# Backplane_v2.net
KiCad netlist of a schematic drawn in EAGLE
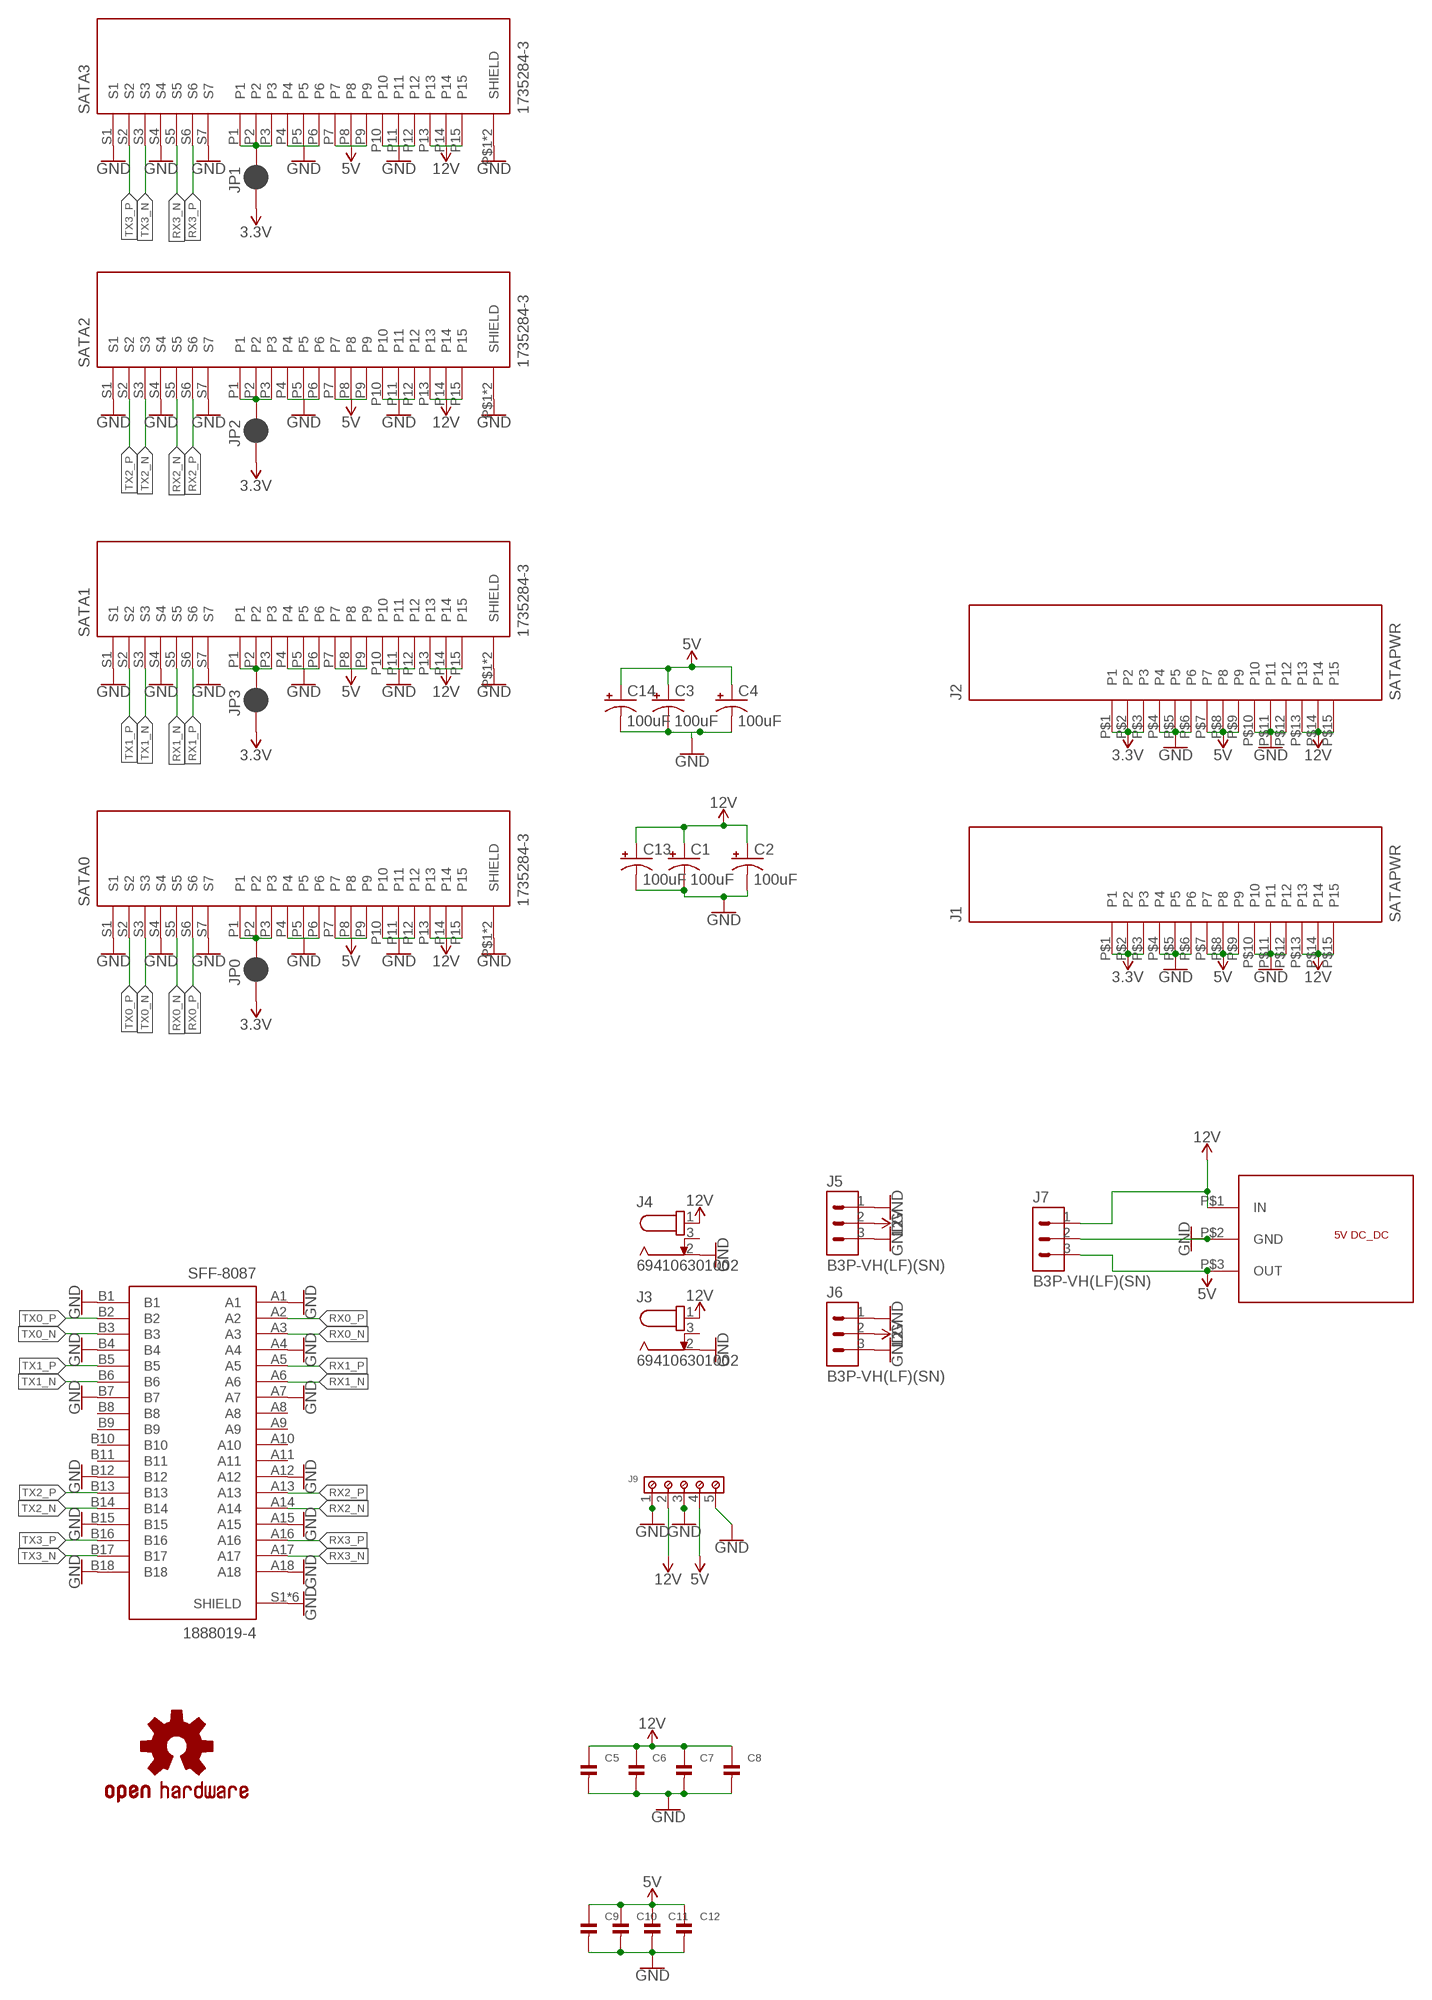
[diagram p0: schematic, sheet 1]

(export (version "E")
  (design (tool "Eeschema 10.0.6"))
  (components
    (comp (ref "C1")
      (value "100uF")
      (footprint "eagle-import:PANASONIC_D")
      (libsource (lib "eagle-import") (part "100UF-POLAR-25V-20%(ELEC)"))
    )
    (comp (ref "C2")
      (value "100uF")
      (footprint "eagle-import:PANASONIC_D")
      (libsource (lib "eagle-import") (part "100UF-POLAR-25V-20%(ELEC)"))
    )
    (comp (ref "C3")
      (value "100uF")
      (footprint "eagle-import:PANASONIC_D")
      (libsource (lib "eagle-import") (part "100UF-POLAR-25V-20%(ELEC)"))
    )
    (comp (ref "C4")
      (value "100uF")
      (footprint "eagle-import:PANASONIC_D")
      (libsource (lib "eagle-import") (part "100UF-POLAR-25V-20%(ELEC)"))
    )
    (comp (ref "C5")
      (value "CAP_CERAMIC0805")
      (footprint "eagle-import:C0805")
      (libsource (lib "eagle-import") (part "CAP_CERAMIC0805"))
    )
    (comp (ref "C6")
      (value "CAP_CERAMIC0805")
      (footprint "eagle-import:C0805")
      (libsource (lib "eagle-import") (part "CAP_CERAMIC0805"))
    )
    (comp (ref "C7")
      (value "CAP_CERAMIC0805")
      (footprint "eagle-import:C0805")
      (libsource (lib "eagle-import") (part "CAP_CERAMIC0805"))
    )
    (comp (ref "C8")
      (value "CAP_CERAMIC0805")
      (footprint "eagle-import:C0805")
      (libsource (lib "eagle-import") (part "CAP_CERAMIC0805"))
    )
    (comp (ref "C9")
      (value "CAP_CERAMIC0805")
      (footprint "eagle-import:C0805")
      (libsource (lib "eagle-import") (part "CAP_CERAMIC0805"))
    )
    (comp (ref "C10")
      (value "CAP_CERAMIC0805")
      (footprint "eagle-import:C0805")
      (libsource (lib "eagle-import") (part "CAP_CERAMIC0805"))
    )
    (comp (ref "C11")
      (value "CAP_CERAMIC0805")
      (footprint "eagle-import:C0805")
      (libsource (lib "eagle-import") (part "CAP_CERAMIC0805"))
    )
    (comp (ref "C12")
      (value "CAP_CERAMIC0805")
      (footprint "eagle-import:C0805")
      (libsource (lib "eagle-import") (part "CAP_CERAMIC0805"))
    )
    (comp (ref "C13")
      (value "100uF")
      (footprint "eagle-import:PANASONIC_D")
      (libsource (lib "eagle-import") (part "100UF-POLAR-25V-20%(ELEC)"))
    )
    (comp (ref "C14")
      (value "100uF")
      (footprint "eagle-import:PANASONIC_D")
      (libsource (lib "eagle-import") (part "100UF-POLAR-25V-20%(ELEC)"))
    )
    (comp (ref "J1")
      (value "SATAPWR")
      (footprint "eagle-import:PTH_90")
      (libsource (lib "eagle-import") (part "SATAPWR"))
    )
    (comp (ref "J2")
      (value "SATAPWR")
      (footprint "eagle-import:PTH_90")
      (libsource (lib "eagle-import") (part "SATAPWR"))
    )
    (comp (ref "J3")
      (value "694106301002")
      (footprint "eagle-import:694106301002")
      (fields
        (field (name "DIGIKEY_PART_NUMBER") "732-5930-ND")
        (field (name "MANUFACTURER") "Wurth Electronics Inc.")
        (field (name "CREATED_BY") "PCBLayout.com")
      )
      (libsource (lib "eagle-import") (part "694106301002"))
    )
    (comp (ref "J4")
      (value "694106301002")
      (footprint "eagle-import:694106301002")
      (fields
        (field (name "DIGIKEY_PART_NUMBER") "732-5930-ND")
        (field (name "MANUFACTURER") "Wurth Electronics Inc.")
        (field (name "CREATED_BY") "PCBLayout.com")
      )
      (libsource (lib "eagle-import") (part "694106301002"))
    )
    (comp (ref "J5")
      (value "B3P-VH(LF)(SN)")
      (footprint "eagle-import:HDR-03")
      (fields
        (field (name "DIGIKEY_PART_NUMBER") "455-1640-ND")
        (field (name "MANUFACTURER") "JST Sales America Inc.")
        (field (name "CREATED_BY") "PCBLayout.com")
      )
      (libsource (lib "eagle-import") (part "B3P-VH(LF)(SN)"))
    )
    (comp (ref "J6")
      (value "B3P-VH(LF)(SN)")
      (footprint "eagle-import:HDR-03")
      (fields
        (field (name "DIGIKEY_PART_NUMBER") "455-1640-ND")
        (field (name "MANUFACTURER") "JST Sales America Inc.")
        (field (name "CREATED_BY") "PCBLayout.com")
      )
      (libsource (lib "eagle-import") (part "B3P-VH(LF)(SN)"))
    )
    (comp (ref "J7")
      (value "B3P-VH(LF)(SN)")
      (footprint "eagle-import:HDR-03")
      (fields
        (field (name "DIGIKEY_PART_NUMBER") "455-1640-ND")
        (field (name "MANUFACTURER") "JST Sales America Inc.")
        (field (name "CREATED_BY") "PCBLayout.com")
      )
      (libsource (lib "eagle-import") (part "B3P-VH(LF)(SN)"))
    )
    (comp (ref "J9")
      (value "691243410005")
      (footprint "eagle-import:691243410005")
      (libsource (lib "eagle-import") (part "691243410005"))
    )
    (comp (ref "JP0")
      (value "JUMPER-SMT_2_NC_PASTE_SILK")
      (footprint "eagle-import:SMT-JUMPER_2_NC_PASTE_SILK")
      (libsource (lib "eagle-import") (part "JUMPER-SMT_2_NC_PASTE_SILK"))
    )
    (comp (ref "JP1")
      (value "JUMPER-SMT_2_NC_PASTE_SILK")
      (footprint "eagle-import:SMT-JUMPER_2_NC_PASTE_SILK")
      (libsource (lib "eagle-import") (part "JUMPER-SMT_2_NC_PASTE_SILK"))
    )
    (comp (ref "JP2")
      (value "JUMPER-SMT_2_NC_PASTE_SILK")
      (footprint "eagle-import:SMT-JUMPER_2_NC_PASTE_SILK")
      (libsource (lib "eagle-import") (part "JUMPER-SMT_2_NC_PASTE_SILK"))
    )
    (comp (ref "JP3")
      (value "JUMPER-SMT_2_NC_PASTE_SILK")
      (footprint "eagle-import:SMT-JUMPER_2_NC_PASTE_SILK")
      (libsource (lib "eagle-import") (part "JUMPER-SMT_2_NC_PASTE_SILK"))
    )
    (comp (ref "LOGO1")
      (value "OSHW-LOGOL")
      (footprint "eagle-import:OSHW-LOGO-L")
      (libsource (lib "eagle-import") (part "OSHW-LOGOL"))
    )
    (comp (ref "SATA0")
      (value "1735284-3")
      (footprint "eagle-import:TE_2023246-2")
      (fields (field (name "COMMENT") "2023246-2") (field (name "MF") "TE Connectivity"))
      (libsource (lib "eagle-import") (part "2023246-21735284-3"))
    )
    (comp (ref "SATA1")
      (value "1735284-3")
      (footprint "eagle-import:TE_2023246-2")
      (fields (field (name "COMMENT") "2023246-2") (field (name "MF") "TE Connectivity"))
      (libsource (lib "eagle-import") (part "2023246-21735284-3"))
    )
    (comp (ref "SATA2")
      (value "1735284-3")
      (footprint "eagle-import:TE_2023246-2")
      (fields (field (name "COMMENT") "2023246-2") (field (name "MF") "TE Connectivity"))
      (libsource (lib "eagle-import") (part "2023246-21735284-3"))
    )
    (comp (ref "SATA3")
      (value "1735284-3")
      (footprint "eagle-import:TE_2023246-2")
      (fields (field (name "COMMENT") "2023246-2") (field (name "MF") "TE Connectivity"))
      (libsource (lib "eagle-import") (part "2023246-21735284-3"))
    )
    (comp (ref "SFF-8087")
      (value "1888019-4")
      (footprint "eagle-import:TE_1888019-4")
      (fields (field (name "DIGI-KEY_PART_NUMBER") "A111092CT-ND") (field (name "MF") "TE Connectivity"))
      (libsource (lib "eagle-import") (part "1888019-4"))
    )
    (comp (ref "U$1")
      (value "5V_DC_DC")
      (footprint "eagle-import:5V_15W_DC_DC")
      (libsource (lib "eagle-import") (part "5V_DC_DC"))
    )
  )
  (nets
    (net (code "1") (name "3.3V") (class "Default")
      (node (ref "J1") (pin "P$1") (pinfunction "P1_P$1") (pintype "passive"))
      (node (ref "J1") (pin "P$2") (pinfunction "P2_P$2") (pintype "passive"))
      (node (ref "J1") (pin "P$3") (pinfunction "P3_P$3") (pintype "passive"))
      (node (ref "J2") (pin "P$1") (pinfunction "P1_P$1") (pintype "passive"))
      (node (ref "J2") (pin "P$2") (pinfunction "P2_P$2") (pintype "passive"))
      (node (ref "J2") (pin "P$3") (pinfunction "P3_P$3") (pintype "passive"))
      (node (ref "JP0") (pin "1") (pinfunction "1_1") (pintype "passive"))
      (node (ref "JP1") (pin "1") (pinfunction "1_1") (pintype "passive"))
      (node (ref "JP2") (pin "1") (pinfunction "1_1") (pintype "passive"))
      (node (ref "JP3") (pin "1") (pinfunction "1_1") (pintype "passive"))
    )
    (net (code "2") (name "5V") (class "Default")
      (node (ref "C10") (pin "1") (pinfunction "P$1_1") (pintype "passive"))
      (node (ref "C11") (pin "1") (pinfunction "P$1_1") (pintype "passive"))
      (node (ref "C12") (pin "1") (pinfunction "P$1_1") (pintype "passive"))
      (node (ref "C14") (pin "+") (pinfunction "+_+") (pintype "passive"))
      (node (ref "C3") (pin "+") (pinfunction "+_+") (pintype "passive"))
      (node (ref "C4") (pin "+") (pinfunction "+_+") (pintype "passive"))
      (node (ref "C9") (pin "1") (pinfunction "P$1_1") (pintype "passive"))
      (node (ref "J1") (pin "P$7") (pinfunction "P7_P$7") (pintype "passive"))
      (node (ref "J1") (pin "P$8") (pinfunction "P8_P$8") (pintype "passive"))
      (node (ref "J1") (pin "P$9") (pinfunction "P9_P$9") (pintype "passive"))
      (node (ref "J2") (pin "P$7") (pinfunction "P7_P$7") (pintype "passive"))
      (node (ref "J2") (pin "P$8") (pinfunction "P8_P$8") (pintype "passive"))
      (node (ref "J2") (pin "P$9") (pinfunction "P9_P$9") (pintype "passive"))
      (node (ref "J7") (pin "3") (pinfunction "3_3") (pintype "passive"))
      (node (ref "J9") (pin "4") (pinfunction "4_4") (pintype "passive"))
      (node (ref "SATA0") (pin "P7") (pinfunction "P7_P7") (pintype "passive"))
      (node (ref "SATA0") (pin "P8") (pinfunction "P8_P8") (pintype "passive"))
      (node (ref "SATA0") (pin "P9") (pinfunction "P9_P9") (pintype "passive"))
      (node (ref "SATA1") (pin "P7") (pinfunction "P7_P7") (pintype "passive"))
      (node (ref "SATA1") (pin "P8") (pinfunction "P8_P8") (pintype "passive"))
      (node (ref "SATA1") (pin "P9") (pinfunction "P9_P9") (pintype "passive"))
      (node (ref "SATA2") (pin "P7") (pinfunction "P7_P7") (pintype "passive"))
      (node (ref "SATA2") (pin "P8") (pinfunction "P8_P8") (pintype "passive"))
      (node (ref "SATA2") (pin "P9") (pinfunction "P9_P9") (pintype "passive"))
      (node (ref "SATA3") (pin "P7") (pinfunction "P7_P7") (pintype "passive"))
      (node (ref "SATA3") (pin "P8") (pinfunction "P8_P8") (pintype "passive"))
      (node (ref "SATA3") (pin "P9") (pinfunction "P9_P9") (pintype "passive"))
      (node (ref "U$1") (pin "P$3") (pinfunction "OUT_P$3") (pintype "bidirectional"))
    )
    (net (code "3") (name "12V") (class "Default")
      (node (ref "C1") (pin "+") (pinfunction "+_+") (pintype "passive"))
      (node (ref "C13") (pin "+") (pinfunction "+_+") (pintype "passive"))
      (node (ref "C2") (pin "+") (pinfunction "+_+") (pintype "passive"))
      (node (ref "C5") (pin "1") (pinfunction "P$1_1") (pintype "passive"))
      (node (ref "C6") (pin "1") (pinfunction "P$1_1") (pintype "passive"))
      (node (ref "C7") (pin "1") (pinfunction "P$1_1") (pintype "passive"))
      (node (ref "C8") (pin "1") (pinfunction "P$1_1") (pintype "passive"))
      (node (ref "J1") (pin "P$13") (pinfunction "P13_P$13") (pintype "passive"))
      (node (ref "J1") (pin "P$14") (pinfunction "P14_P$14") (pintype "passive"))
      (node (ref "J1") (pin "P$15") (pinfunction "P15_P$15") (pintype "passive"))
      (node (ref "J2") (pin "P$13") (pinfunction "P13_P$13") (pintype "passive"))
      (node (ref "J2") (pin "P$14") (pinfunction "P14_P$14") (pintype "passive"))
      (node (ref "J2") (pin "P$15") (pinfunction "P15_P$15") (pintype "passive"))
      (node (ref "J3") (pin "1") (pinfunction "1_1") (pintype "passive"))
      (node (ref "J4") (pin "1") (pinfunction "1_1") (pintype "passive"))
      (node (ref "J5") (pin "2") (pinfunction "2_2") (pintype "passive"))
      (node (ref "J6") (pin "2") (pinfunction "2_2") (pintype "passive"))
      (node (ref "J7") (pin "1") (pinfunction "1_1") (pintype "passive"))
      (node (ref "J9") (pin "2") (pinfunction "2_2") (pintype "passive"))
      (node (ref "SATA0") (pin "P13") (pinfunction "P13_P13") (pintype "passive"))
      (node (ref "SATA0") (pin "P14") (pinfunction "P14_P14") (pintype "passive"))
      (node (ref "SATA0") (pin "P15") (pinfunction "P15_P15") (pintype "passive"))
      (node (ref "SATA1") (pin "P13") (pinfunction "P13_P13") (pintype "passive"))
      (node (ref "SATA1") (pin "P14") (pinfunction "P14_P14") (pintype "passive"))
      (node (ref "SATA1") (pin "P15") (pinfunction "P15_P15") (pintype "passive"))
      (node (ref "SATA2") (pin "P13") (pinfunction "P13_P13") (pintype "passive"))
      (node (ref "SATA2") (pin "P14") (pinfunction "P14_P14") (pintype "passive"))
      (node (ref "SATA2") (pin "P15") (pinfunction "P15_P15") (pintype "passive"))
      (node (ref "SATA3") (pin "P13") (pinfunction "P13_P13") (pintype "passive"))
      (node (ref "SATA3") (pin "P14") (pinfunction "P14_P14") (pintype "passive"))
      (node (ref "SATA3") (pin "P15") (pinfunction "P15_P15") (pintype "passive"))
      (node (ref "U$1") (pin "P$1") (pinfunction "IN_P$1") (pintype "bidirectional"))
    )
    (net (code "4") (name "GND") (class "Default")
      (node (ref "C1") (pin "-") (pinfunction "-_-") (pintype "passive"))
      (node (ref "C10") (pin "2") (pinfunction "P$2_2") (pintype "passive"))
      (node (ref "C11") (pin "2") (pinfunction "P$2_2") (pintype "passive"))
      (node (ref "C12") (pin "2") (pinfunction "P$2_2") (pintype "passive"))
      (node (ref "C13") (pin "-") (pinfunction "-_-") (pintype "passive"))
      (node (ref "C14") (pin "-") (pinfunction "-_-") (pintype "passive"))
      (node (ref "C2") (pin "-") (pinfunction "-_-") (pintype "passive"))
      (node (ref "C3") (pin "-") (pinfunction "-_-") (pintype "passive"))
      (node (ref "C4") (pin "-") (pinfunction "-_-") (pintype "passive"))
      (node (ref "C5") (pin "2") (pinfunction "P$2_2") (pintype "passive"))
      (node (ref "C6") (pin "2") (pinfunction "P$2_2") (pintype "passive"))
      (node (ref "C7") (pin "2") (pinfunction "P$2_2") (pintype "passive"))
      (node (ref "C8") (pin "2") (pinfunction "P$2_2") (pintype "passive"))
      (node (ref "C9") (pin "2") (pinfunction "P$2_2") (pintype "passive"))
      (node (ref "J1") (pin "P$10") (pinfunction "P10_P$10") (pintype "passive"))
      (node (ref "J1") (pin "P$11") (pinfunction "P11_P$11") (pintype "passive"))
      (node (ref "J1") (pin "P$12") (pinfunction "P12_P$12") (pintype "passive"))
      (node (ref "J1") (pin "P$4") (pinfunction "P4_P$4") (pintype "passive"))
      (node (ref "J1") (pin "P$5") (pinfunction "P5_P$5") (pintype "passive"))
      (node (ref "J1") (pin "P$6") (pinfunction "P6_P$6") (pintype "passive"))
      (node (ref "J2") (pin "P$10") (pinfunction "P10_P$10") (pintype "passive"))
      (node (ref "J2") (pin "P$11") (pinfunction "P11_P$11") (pintype "passive"))
      (node (ref "J2") (pin "P$12") (pinfunction "P12_P$12") (pintype "passive"))
      (node (ref "J2") (pin "P$4") (pinfunction "P4_P$4") (pintype "passive"))
      (node (ref "J2") (pin "P$5") (pinfunction "P5_P$5") (pintype "passive"))
      (node (ref "J2") (pin "P$6") (pinfunction "P6_P$6") (pintype "passive"))
      (node (ref "J3") (pin "2") (pinfunction "2_2") (pintype "passive"))
      (node (ref "J4") (pin "2") (pinfunction "2_2") (pintype "passive"))
      (node (ref "J5") (pin "1") (pinfunction "1_1") (pintype "passive"))
      (node (ref "J5") (pin "3") (pinfunction "3_3") (pintype "passive"))
      (node (ref "J6") (pin "1") (pinfunction "1_1") (pintype "passive"))
      (node (ref "J6") (pin "3") (pinfunction "3_3") (pintype "passive"))
      (node (ref "J7") (pin "2") (pinfunction "2_2") (pintype "passive"))
      (node (ref "J9") (pin "1") (pinfunction "1_1") (pintype "passive"))
      (node (ref "J9") (pin "3") (pinfunction "3_3") (pintype "passive"))
      (node (ref "J9") (pin "5") (pinfunction "5_5") (pintype "passive"))
      (node (ref "SATA0") (pin "P$1") (pinfunction "SHIELD_P$1") (pintype "passive"))
      (node (ref "SATA0") (pin "P$2") (pinfunction "SHIELD_P$2") (pintype "passive"))
      (node (ref "SATA0") (pin "P10") (pinfunction "P10_P10") (pintype "passive"))
      (node (ref "SATA0") (pin "P11") (pinfunction "P11_P11") (pintype "passive"))
      (node (ref "SATA0") (pin "P12") (pinfunction "P12_P12") (pintype "passive"))
      (node (ref "SATA0") (pin "P4") (pinfunction "P4_P4") (pintype "passive"))
      (node (ref "SATA0") (pin "P5") (pinfunction "P5_P5") (pintype "passive"))
      (node (ref "SATA0") (pin "P6") (pinfunction "P6_P6") (pintype "passive"))
      (node (ref "SATA0") (pin "S1") (pinfunction "S1_S1") (pintype "passive"))
      (node (ref "SATA0") (pin "S4") (pinfunction "S4_S4") (pintype "passive"))
      (node (ref "SATA0") (pin "S7") (pinfunction "S7_S7") (pintype "passive"))
      (node (ref "SATA1") (pin "P$1") (pinfunction "SHIELD_P$1") (pintype "passive"))
      (node (ref "SATA1") (pin "P$2") (pinfunction "SHIELD_P$2") (pintype "passive"))
      (node (ref "SATA1") (pin "P10") (pinfunction "P10_P10") (pintype "passive"))
      (node (ref "SATA1") (pin "P11") (pinfunction "P11_P11") (pintype "passive"))
      (node (ref "SATA1") (pin "P12") (pinfunction "P12_P12") (pintype "passive"))
      (node (ref "SATA1") (pin "P4") (pinfunction "P4_P4") (pintype "passive"))
      (node (ref "SATA1") (pin "P5") (pinfunction "P5_P5") (pintype "passive"))
      (node (ref "SATA1") (pin "P6") (pinfunction "P6_P6") (pintype "passive"))
      (node (ref "SATA1") (pin "S1") (pinfunction "S1_S1") (pintype "passive"))
      (node (ref "SATA1") (pin "S4") (pinfunction "S4_S4") (pintype "passive"))
      (node (ref "SATA1") (pin "S7") (pinfunction "S7_S7") (pintype "passive"))
      (node (ref "SATA2") (pin "P$1") (pinfunction "SHIELD_P$1") (pintype "passive"))
      (node (ref "SATA2") (pin "P$2") (pinfunction "SHIELD_P$2") (pintype "passive"))
      (node (ref "SATA2") (pin "P10") (pinfunction "P10_P10") (pintype "passive"))
      (node (ref "SATA2") (pin "P11") (pinfunction "P11_P11") (pintype "passive"))
      (node (ref "SATA2") (pin "P12") (pinfunction "P12_P12") (pintype "passive"))
      (node (ref "SATA2") (pin "P4") (pinfunction "P4_P4") (pintype "passive"))
      (node (ref "SATA2") (pin "P5") (pinfunction "P5_P5") (pintype "passive"))
      (node (ref "SATA2") (pin "P6") (pinfunction "P6_P6") (pintype "passive"))
      (node (ref "SATA2") (pin "S1") (pinfunction "S1_S1") (pintype "passive"))
      (node (ref "SATA2") (pin "S4") (pinfunction "S4_S4") (pintype "passive"))
      (node (ref "SATA2") (pin "S7") (pinfunction "S7_S7") (pintype "passive"))
      (node (ref "SATA3") (pin "P$1") (pinfunction "SHIELD_P$1") (pintype "passive"))
      (node (ref "SATA3") (pin "P$2") (pinfunction "SHIELD_P$2") (pintype "passive"))
      (node (ref "SATA3") (pin "P10") (pinfunction "P10_P10") (pintype "passive"))
      (node (ref "SATA3") (pin "P11") (pinfunction "P11_P11") (pintype "passive"))
      (node (ref "SATA3") (pin "P12") (pinfunction "P12_P12") (pintype "passive"))
      (node (ref "SATA3") (pin "P4") (pinfunction "P4_P4") (pintype "passive"))
      (node (ref "SATA3") (pin "P5") (pinfunction "P5_P5") (pintype "passive"))
      (node (ref "SATA3") (pin "P6") (pinfunction "P6_P6") (pintype "passive"))
      (node (ref "SATA3") (pin "S1") (pinfunction "S1_S1") (pintype "passive"))
      (node (ref "SATA3") (pin "S4") (pinfunction "S4_S4") (pintype "passive"))
      (node (ref "SATA3") (pin "S7") (pinfunction "S7_S7") (pintype "passive"))
      (node (ref "SFF-8087") (pin "A1") (pinfunction "A1_A1") (pintype "passive"))
      (node (ref "SFF-8087") (pin "A12") (pinfunction "A12_A12") (pintype "passive"))
      (node (ref "SFF-8087") (pin "A15") (pinfunction "A15_A15") (pintype "passive"))
      (node (ref "SFF-8087") (pin "A18") (pinfunction "A18_A18") (pintype "passive"))
      (node (ref "SFF-8087") (pin "A4") (pinfunction "A4_A4") (pintype "passive"))
      (node (ref "SFF-8087") (pin "A7") (pinfunction "A7_A7") (pintype "passive"))
      (node (ref "SFF-8087") (pin "B1") (pinfunction "B1_B1") (pintype "passive"))
      (node (ref "SFF-8087") (pin "B12") (pinfunction "B12_B12") (pintype "passive"))
      (node (ref "SFF-8087") (pin "B15") (pinfunction "B15_B15") (pintype "passive"))
      (node (ref "SFF-8087") (pin "B18") (pinfunction "B18_B18") (pintype "passive"))
      (node (ref "SFF-8087") (pin "B4") (pinfunction "B4_B4") (pintype "passive"))
      (node (ref "SFF-8087") (pin "B7") (pinfunction "B7_B7") (pintype "passive"))
      (node (ref "SFF-8087") (pin "S1") (pinfunction "SHIELD_S1") (pintype "passive"))
      (node (ref "SFF-8087") (pin "S2") (pinfunction "SHIELD_S2") (pintype "passive"))
      (node (ref "SFF-8087") (pin "S3") (pinfunction "SHIELD_S3") (pintype "passive"))
      (node (ref "SFF-8087") (pin "S4") (pinfunction "SHIELD_S4") (pintype "passive"))
      (node (ref "SFF-8087") (pin "S5") (pinfunction "SHIELD_S5") (pintype "passive"))
      (node (ref "SFF-8087") (pin "S6") (pinfunction "SHIELD_S6") (pintype "passive"))
      (node (ref "U$1") (pin "P$2") (pinfunction "GND_P$2") (pintype "bidirectional"))
    )
    (net (code "5") (name "Net-(JP0-Pad2)") (class "Default")
      (node (ref "JP0") (pin "2") (pinfunction "2_2") (pintype "passive"))
      (node (ref "SATA0") (pin "P1") (pinfunction "P1_P1") (pintype "passive"))
      (node (ref "SATA0") (pin "P2") (pinfunction "P2_P2") (pintype "passive"))
      (node (ref "SATA0") (pin "P3") (pinfunction "P3_P3") (pintype "passive"))
    )
    (net (code "6") (name "Net-(JP1-Pad2)") (class "Default")
      (node (ref "JP1") (pin "2") (pinfunction "2_2") (pintype "passive"))
      (node (ref "SATA3") (pin "P1") (pinfunction "P1_P1") (pintype "passive"))
      (node (ref "SATA3") (pin "P2") (pinfunction "P2_P2") (pintype "passive"))
      (node (ref "SATA3") (pin "P3") (pinfunction "P3_P3") (pintype "passive"))
    )
    (net (code "7") (name "Net-(JP2-Pad2)") (class "Default")
      (node (ref "JP2") (pin "2") (pinfunction "2_2") (pintype "passive"))
      (node (ref "SATA2") (pin "P1") (pinfunction "P1_P1") (pintype "passive"))
      (node (ref "SATA2") (pin "P2") (pinfunction "P2_P2") (pintype "passive"))
      (node (ref "SATA2") (pin "P3") (pinfunction "P3_P3") (pintype "passive"))
    )
    (net (code "8") (name "Net-(JP3-Pad2)") (class "Default")
      (node (ref "JP3") (pin "2") (pinfunction "2_2") (pintype "passive"))
      (node (ref "SATA1") (pin "P1") (pinfunction "P1_P1") (pintype "passive"))
      (node (ref "SATA1") (pin "P2") (pinfunction "P2_P2") (pintype "passive"))
      (node (ref "SATA1") (pin "P3") (pinfunction "P3_P3") (pintype "passive"))
    )
    (net (code "9") (name "RX0_N") (class "Default")
      (node (ref "SATA0") (pin "S5") (pinfunction "S5_S5") (pintype "passive"))
      (node (ref "SFF-8087") (pin "A3") (pinfunction "A3_A3") (pintype "passive"))
    )
    (net (code "10") (name "RX0_P") (class "Default")
      (node (ref "SATA0") (pin "S6") (pinfunction "S6_S6") (pintype "passive"))
      (node (ref "SFF-8087") (pin "A2") (pinfunction "A2_A2") (pintype "passive"))
    )
    (net (code "11") (name "RX1_N") (class "Default")
      (node (ref "SATA1") (pin "S5") (pinfunction "S5_S5") (pintype "passive"))
      (node (ref "SFF-8087") (pin "A6") (pinfunction "A6_A6") (pintype "passive"))
    )
    (net (code "12") (name "RX1_P") (class "Default")
      (node (ref "SATA1") (pin "S6") (pinfunction "S6_S6") (pintype "passive"))
      (node (ref "SFF-8087") (pin "A5") (pinfunction "A5_A5") (pintype "passive"))
    )
    (net (code "13") (name "RX2_N") (class "Default")
      (node (ref "SATA2") (pin "S5") (pinfunction "S5_S5") (pintype "passive"))
      (node (ref "SFF-8087") (pin "A14") (pinfunction "A14_A14") (pintype "passive"))
    )
    (net (code "14") (name "RX2_P") (class "Default")
      (node (ref "SATA2") (pin "S6") (pinfunction "S6_S6") (pintype "passive"))
      (node (ref "SFF-8087") (pin "A13") (pinfunction "A13_A13") (pintype "passive"))
    )
    (net (code "15") (name "RX3_N") (class "Default")
      (node (ref "SATA3") (pin "S5") (pinfunction "S5_S5") (pintype "passive"))
      (node (ref "SFF-8087") (pin "A17") (pinfunction "A17_A17") (pintype "passive"))
    )
    (net (code "16") (name "RX3_P") (class "Default")
      (node (ref "SATA3") (pin "S6") (pinfunction "S6_S6") (pintype "passive"))
      (node (ref "SFF-8087") (pin "A16") (pinfunction "A16_A16") (pintype "passive"))
    )
    (net (code "17") (name "TX0_N") (class "Default")
      (node (ref "SATA0") (pin "S3") (pinfunction "S3_S3") (pintype "passive"))
      (node (ref "SFF-8087") (pin "B3") (pinfunction "B3_B3") (pintype "passive"))
    )
    (net (code "18") (name "TX0_P") (class "Default")
      (node (ref "SATA0") (pin "S2") (pinfunction "S2_S2") (pintype "passive"))
      (node (ref "SFF-8087") (pin "B2") (pinfunction "B2_B2") (pintype "passive"))
    )
    (net (code "19") (name "TX1_N") (class "Default")
      (node (ref "SATA1") (pin "S3") (pinfunction "S3_S3") (pintype "passive"))
      (node (ref "SFF-8087") (pin "B6") (pinfunction "B6_B6") (pintype "passive"))
    )
    (net (code "20") (name "TX1_P") (class "Default")
      (node (ref "SATA1") (pin "S2") (pinfunction "S2_S2") (pintype "passive"))
      (node (ref "SFF-8087") (pin "B5") (pinfunction "B5_B5") (pintype "passive"))
    )
    (net (code "21") (name "TX2_N") (class "Default")
      (node (ref "SATA2") (pin "S3") (pinfunction "S3_S3") (pintype "passive"))
      (node (ref "SFF-8087") (pin "B14") (pinfunction "B14_B14") (pintype "passive"))
    )
    (net (code "22") (name "TX2_P") (class "Default")
      (node (ref "SATA2") (pin "S2") (pinfunction "S2_S2") (pintype "passive"))
      (node (ref "SFF-8087") (pin "B13") (pinfunction "B13_B13") (pintype "passive"))
    )
    (net (code "23") (name "TX3_N") (class "Default")
      (node (ref "SATA3") (pin "S3") (pinfunction "S3_S3") (pintype "passive"))
      (node (ref "SFF-8087") (pin "B17") (pinfunction "B17_B17") (pintype "passive"))
    )
    (net (code "24") (name "TX3_P") (class "Default")
      (node (ref "SATA3") (pin "S2") (pinfunction "S2_S2") (pintype "passive"))
      (node (ref "SFF-8087") (pin "B16") (pinfunction "B16_B16") (pintype "passive"))
    )
    (net (code "25") (name "unconnected-(J3-Pad3)") (class "Default")
      (node (ref "J3") (pin "3") (pinfunction "3_3") (pintype "passive"))
    )
    (net (code "26") (name "unconnected-(J4-Pad3)") (class "Default")
      (node (ref "J4") (pin "3") (pinfunction "3_3") (pintype "passive"))
    )
    (net (code "27") (name "unconnected-(SFF-8087-PadA8)") (class "Default")
      (node (ref "SFF-8087") (pin "A8") (pinfunction "A8_A8") (pintype "passive"))
    )
    (net (code "28") (name "unconnected-(SFF-8087-PadA9)") (class "Default")
      (node (ref "SFF-8087") (pin "A9") (pinfunction "A9_A9") (pintype "passive"))
    )
    (net (code "29") (name "unconnected-(SFF-8087-PadA10)") (class "Default")
      (node (ref "SFF-8087") (pin "A10") (pinfunction "A10_A10") (pintype "passive"))
    )
    (net (code "30") (name "unconnected-(SFF-8087-PadA11)") (class "Default")
      (node (ref "SFF-8087") (pin "A11") (pinfunction "A11_A11") (pintype "passive"))
    )
    (net (code "31") (name "unconnected-(SFF-8087-PadB8)") (class "Default")
      (node (ref "SFF-8087") (pin "B8") (pinfunction "B8_B8") (pintype "passive"))
    )
    (net (code "32") (name "unconnected-(SFF-8087-PadB9)") (class "Default")
      (node (ref "SFF-8087") (pin "B9") (pinfunction "B9_B9") (pintype "passive"))
    )
    (net (code "33") (name "unconnected-(SFF-8087-PadB10)") (class "Default")
      (node (ref "SFF-8087") (pin "B10") (pinfunction "B10_B10") (pintype "passive"))
    )
    (net (code "34") (name "unconnected-(SFF-8087-PadB11)") (class "Default")
      (node (ref "SFF-8087") (pin "B11") (pinfunction "B11_B11") (pintype "passive"))
    )
  )
)
